# FRDM-Shield-Rev1_1.net
KiCad netlist of a schematic drawn in EAGLE
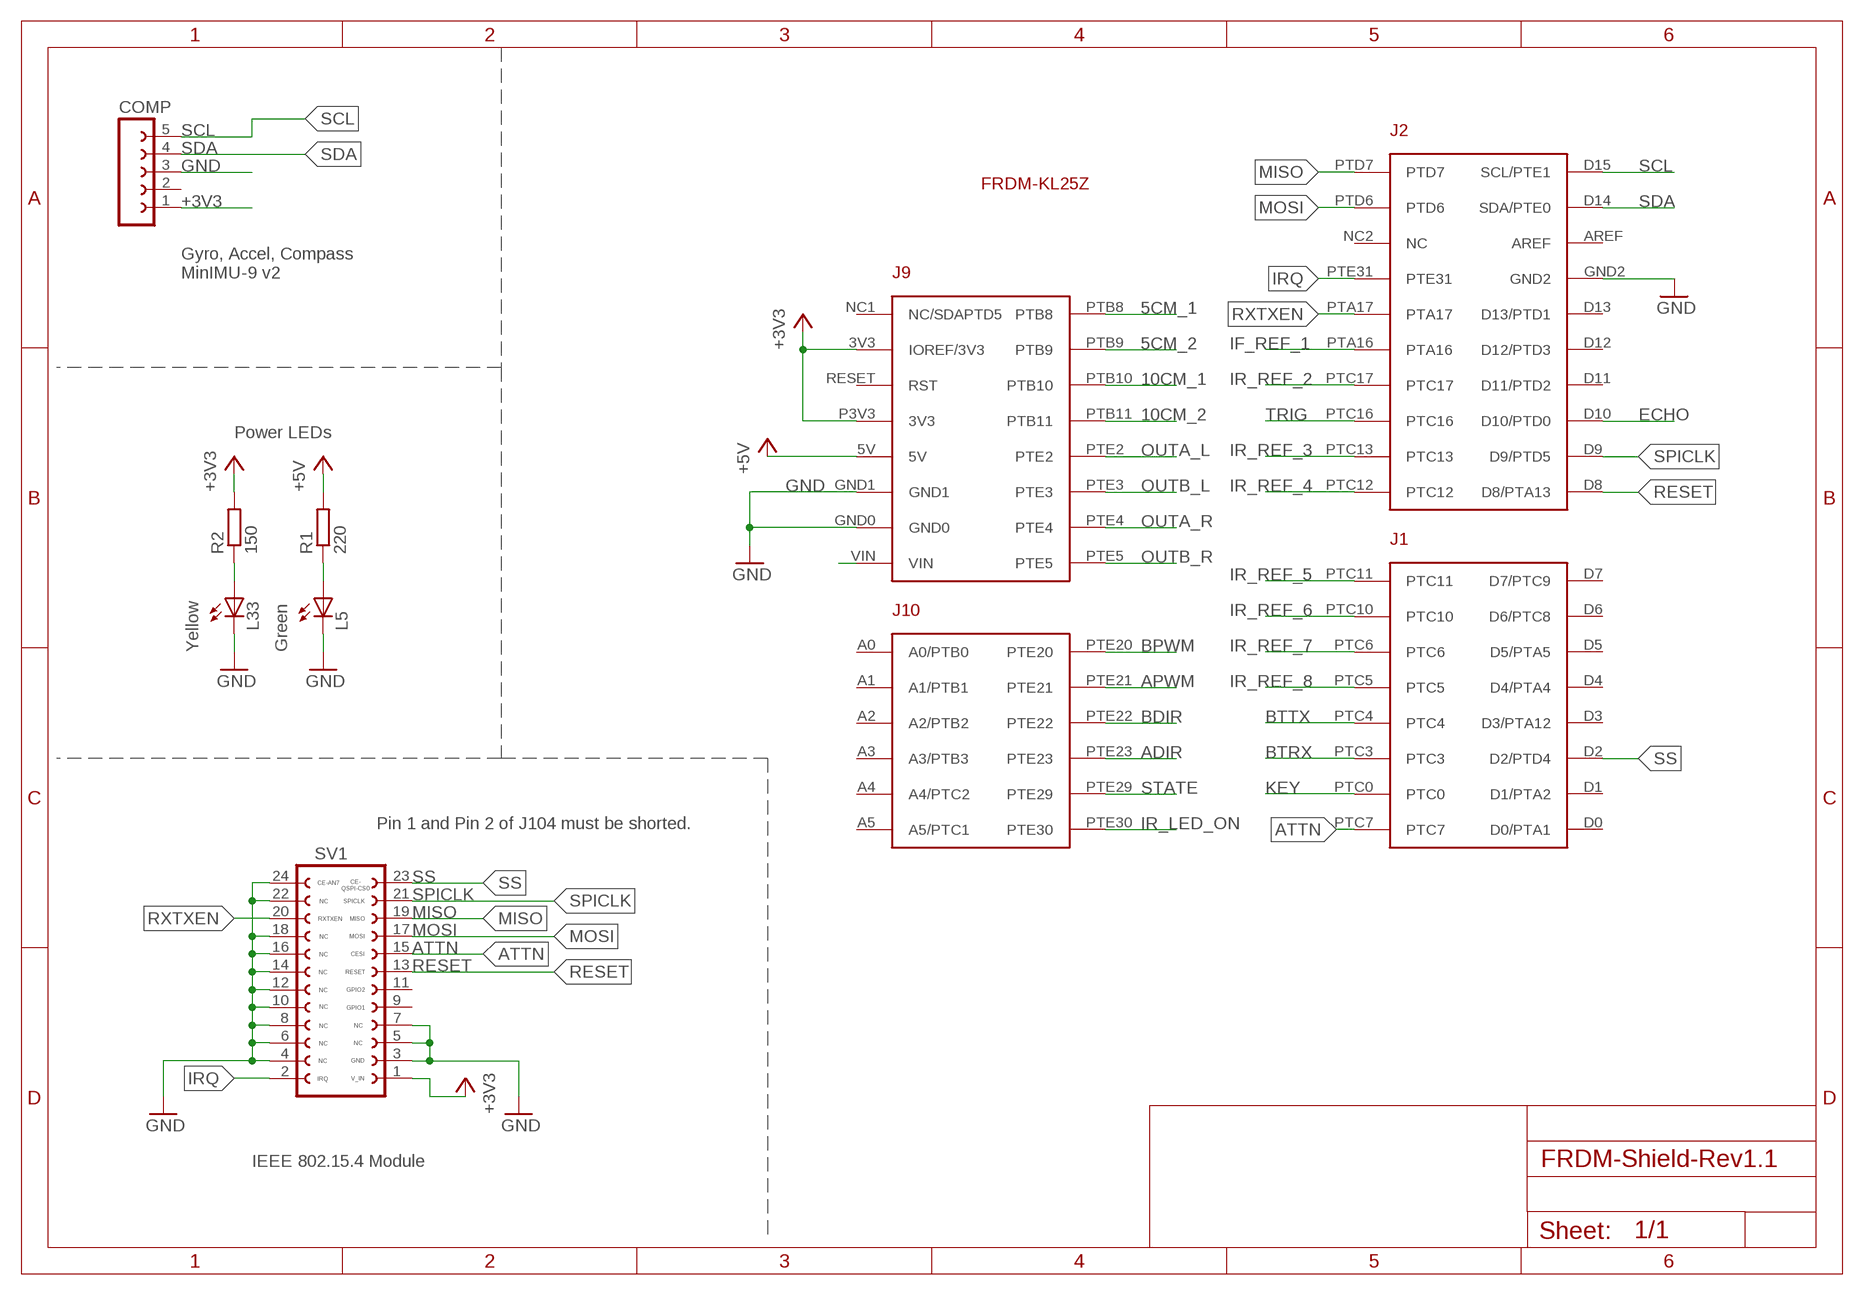
[diagram p0: schematic, sheet 1]

(export (version "E")
  (design (tool "Eeschema 10.0.6"))
  (components
    (comp (ref "COMP")
      (value "FE05-1")
      (footprint "eagle-import:FE05-1")
      (libsource (lib "eagle-import") (part "FE05-1"))
    )
    (comp (ref "FRDM1")
      (value "FRDM-KL25ZARDUINO")
      (footprint "eagle-import:FRDM-KL25Z")
      (libsource (lib "eagle-import") (part "FRDM-KL25ZARDUINO"))
    )
    (comp (ref "L5")
      (value "LEDCHIP-LED0603")
      (footprint "eagle-import:CHIP-LED0603")
      (libsource (lib "eagle-import") (part "LEDCHIP-LED0603"))
    )
    (comp (ref "L33")
      (value "LEDCHIP-LED0603")
      (footprint "eagle-import:CHIP-LED0603")
      (libsource (lib "eagle-import") (part "LEDCHIP-LED0603"))
    )
    (comp (ref "R1")
      (value "220")
      (footprint "eagle-import:M0805")
      (libsource (lib "eagle-import") (part "R-EU_M0805"))
    )
    (comp (ref "R2")
      (value "150")
      (footprint "eagle-import:M0805")
      (libsource (lib "eagle-import") (part "R-EU_M0805"))
    )
    (comp (ref "SV1")
      (value "MC1320X")
      (footprint "eagle-import:FE12-2")
      (libsource (lib "eagle-import") (part "MC1320X"))
    )
  )
  (nets
    (net (code "1") (name "+3V3") (class "Default")
      (node (ref "COMP") (pin "1") (pinfunction "1_1") (pintype "passive"))
      (node (ref "FRDM1") (pin "3V3") (pinfunction "IOREF/3V3_3V3") (pintype "bidirectional"))
      (node (ref "FRDM1") (pin "P3V3") (pinfunction "3V3_P3V3") (pintype "bidirectional"))
      (node (ref "R2") (pin "2") (pinfunction "2_2") (pintype "passive"))
      (node (ref "SV1") (pin "1") (pinfunction "1_1") (pintype "passive"))
    )
    (net (code "2") (name "+5V") (class "Default")
      (node (ref "FRDM1") (pin "5V") (pinfunction "5V_5V") (pintype "bidirectional"))
      (node (ref "R1") (pin "2") (pinfunction "2_2") (pintype "passive"))
    )
    (net (code "3") (name "/5CM_1") (class "Default")
      (node (ref "FRDM1") (pin "PTB8") (pinfunction "PTB8_PTB8") (pintype "bidirectional"))
    )
    (net (code "4") (name "/5CM_2") (class "Default")
      (node (ref "FRDM1") (pin "PTB9") (pinfunction "PTB9_PTB9") (pintype "bidirectional"))
    )
    (net (code "5") (name "/10CM_1") (class "Default")
      (node (ref "FRDM1") (pin "PTB10") (pinfunction "PTB10_PTB10") (pintype "bidirectional"))
    )
    (net (code "6") (name "/10CM_2") (class "Default")
      (node (ref "FRDM1") (pin "PTB11") (pinfunction "PTB11_PTB11") (pintype "bidirectional"))
    )
    (net (code "7") (name "/ADIR") (class "Default")
      (node (ref "FRDM1") (pin "PTE23") (pinfunction "PTE23_PTE23") (pintype "bidirectional"))
    )
    (net (code "8") (name "/APWM") (class "Default")
      (node (ref "FRDM1") (pin "PTE21") (pinfunction "PTE21_PTE21") (pintype "bidirectional"))
    )
    (net (code "9") (name "/BDIR") (class "Default")
      (node (ref "FRDM1") (pin "PTE22") (pinfunction "PTE22_PTE22") (pintype "bidirectional"))
    )
    (net (code "10") (name "/BPWM") (class "Default")
      (node (ref "FRDM1") (pin "PTE20") (pinfunction "PTE20_PTE20") (pintype "bidirectional"))
    )
    (net (code "11") (name "/BTRX") (class "Default")
      (node (ref "FRDM1") (pin "PTC3") (pinfunction "PTC3_PTC3") (pintype "bidirectional"))
    )
    (net (code "12") (name "/BTTX") (class "Default")
      (node (ref "FRDM1") (pin "PTC4") (pinfunction "PTC4_PTC4") (pintype "bidirectional"))
    )
    (net (code "13") (name "/ECHO") (class "Default")
      (node (ref "FRDM1") (pin "D10") (pinfunction "D10/PTD0_D10") (pintype "bidirectional"))
    )
    (net (code "14") (name "/IF_REF_1") (class "Default")
      (node (ref "FRDM1") (pin "PTA16") (pinfunction "PTA16_PTA16") (pintype "bidirectional"))
    )
    (net (code "15") (name "/IR_LED_ON") (class "Default")
      (node (ref "FRDM1") (pin "PTE30") (pinfunction "PTE30_PTE30") (pintype "bidirectional"))
    )
    (net (code "16") (name "/IR_REF_2") (class "Default")
      (node (ref "FRDM1") (pin "PTC17") (pinfunction "PTC17_PTC17") (pintype "bidirectional"))
    )
    (net (code "17") (name "/IR_REF_3") (class "Default")
      (node (ref "FRDM1") (pin "PTC13") (pinfunction "PTC13_PTC13") (pintype "bidirectional"))
    )
    (net (code "18") (name "/IR_REF_4") (class "Default")
      (node (ref "FRDM1") (pin "PTC12") (pinfunction "PTC12_PTC12") (pintype "bidirectional"))
    )
    (net (code "19") (name "/IR_REF_5") (class "Default")
      (node (ref "FRDM1") (pin "PTC11") (pinfunction "PTC11_PTC11") (pintype "bidirectional"))
    )
    (net (code "20") (name "/IR_REF_6") (class "Default")
      (node (ref "FRDM1") (pin "PTC10") (pinfunction "PTC10_PTC10") (pintype "bidirectional"))
    )
    (net (code "21") (name "/IR_REF_7") (class "Default")
      (node (ref "FRDM1") (pin "PTC6") (pinfunction "PTC6_PTC6") (pintype "bidirectional"))
    )
    (net (code "22") (name "/IR_REF_8") (class "Default")
      (node (ref "FRDM1") (pin "PTC5") (pinfunction "PTC5_PTC5") (pintype "bidirectional"))
    )
    (net (code "23") (name "/KEY") (class "Default")
      (node (ref "FRDM1") (pin "PTC0") (pinfunction "PTC0_PTC0") (pintype "bidirectional"))
    )
    (net (code "24") (name "/OUTA_L") (class "Default")
      (node (ref "FRDM1") (pin "PTE2") (pinfunction "PTE2_PTE2") (pintype "bidirectional"))
    )
    (net (code "25") (name "/OUTA_R") (class "Default")
      (node (ref "FRDM1") (pin "PTE4") (pinfunction "PTE4_PTE4") (pintype "bidirectional"))
    )
    (net (code "26") (name "/OUTB_L") (class "Default")
      (node (ref "FRDM1") (pin "PTE3") (pinfunction "PTE3_PTE3") (pintype "bidirectional"))
    )
    (net (code "27") (name "/OUTB_R") (class "Default")
      (node (ref "FRDM1") (pin "PTE5") (pinfunction "PTE5_PTE5") (pintype "bidirectional"))
    )
    (net (code "28") (name "/STATE") (class "Default")
      (node (ref "FRDM1") (pin "PTE29") (pinfunction "PTE29_PTE29") (pintype "bidirectional"))
    )
    (net (code "29") (name "/TRIG") (class "Default")
      (node (ref "FRDM1") (pin "PTC16") (pinfunction "PTC16_PTC16") (pintype "bidirectional"))
    )
    (net (code "30") (name "ATTN") (class "Default")
      (node (ref "FRDM1") (pin "PTC7") (pinfunction "PTC7_PTC7") (pintype "bidirectional"))
      (node (ref "SV1") (pin "15") (pinfunction "15_15") (pintype "passive"))
    )
    (net (code "31") (name "GND") (class "Default")
      (node (ref "COMP") (pin "3") (pinfunction "3_3") (pintype "passive"))
      (node (ref "FRDM1") (pin "GND0") (pinfunction "GND0_GND0") (pintype "bidirectional"))
      (node (ref "FRDM1") (pin "GND1") (pinfunction "GND1_GND1") (pintype "bidirectional"))
      (node (ref "FRDM1") (pin "GND2") (pinfunction "GND2_GND2") (pintype "bidirectional"))
      (node (ref "L33") (pin "C") (pinfunction "C_C") (pintype "passive"))
      (node (ref "L5") (pin "C") (pinfunction "C_C") (pintype "passive"))
      (node (ref "SV1") (pin "10") (pinfunction "10_10") (pintype "passive"))
      (node (ref "SV1") (pin "12") (pinfunction "12_12") (pintype "passive"))
      (node (ref "SV1") (pin "14") (pinfunction "14_14") (pintype "passive"))
      (node (ref "SV1") (pin "16") (pinfunction "16_16") (pintype "passive"))
      (node (ref "SV1") (pin "18") (pinfunction "18_18") (pintype "passive"))
      (node (ref "SV1") (pin "22") (pinfunction "22_22") (pintype "passive"))
      (node (ref "SV1") (pin "24") (pinfunction "24_24") (pintype "passive"))
      (node (ref "SV1") (pin "3") (pinfunction "3_3") (pintype "passive"))
      (node (ref "SV1") (pin "4") (pinfunction "4_4") (pintype "passive"))
      (node (ref "SV1") (pin "5") (pinfunction "5_5") (pintype "passive"))
      (node (ref "SV1") (pin "6") (pinfunction "6_6") (pintype "passive"))
      (node (ref "SV1") (pin "7") (pinfunction "7_7") (pintype "passive"))
      (node (ref "SV1") (pin "8") (pinfunction "8_8") (pintype "passive"))
    )
    (net (code "32") (name "IRQ") (class "Default")
      (node (ref "FRDM1") (pin "PTE31") (pinfunction "PTE31_PTE31") (pintype "bidirectional"))
      (node (ref "SV1") (pin "2") (pinfunction "2_2") (pintype "passive"))
    )
    (net (code "33") (name "MISO") (class "Default")
      (node (ref "FRDM1") (pin "PTD7") (pinfunction "PTD7_PTD7") (pintype "bidirectional"))
      (node (ref "SV1") (pin "19") (pinfunction "19_19") (pintype "passive"))
    )
    (net (code "34") (name "MOSI") (class "Default")
      (node (ref "FRDM1") (pin "PTD6") (pinfunction "PTD6_PTD6") (pintype "bidirectional"))
      (node (ref "SV1") (pin "17") (pinfunction "17_17") (pintype "passive"))
    )
    (net (code "35") (name "Net-(L5-PadA)") (class "Default")
      (node (ref "L5") (pin "A") (pinfunction "A_A") (pintype "passive"))
      (node (ref "R1") (pin "1") (pinfunction "1_1") (pintype "passive"))
    )
    (net (code "36") (name "Net-(L33-PadA)") (class "Default")
      (node (ref "L33") (pin "A") (pinfunction "A_A") (pintype "passive"))
      (node (ref "R2") (pin "1") (pinfunction "1_1") (pintype "passive"))
    )
    (net (code "37") (name "RESET") (class "Default")
      (node (ref "FRDM1") (pin "D8") (pinfunction "D8/PTA13_D8") (pintype "bidirectional"))
      (node (ref "SV1") (pin "13") (pinfunction "13_13") (pintype "passive"))
    )
    (net (code "38") (name "RXTXEN") (class "Default")
      (node (ref "FRDM1") (pin "PTA17") (pinfunction "PTA17_PTA17") (pintype "bidirectional"))
      (node (ref "SV1") (pin "20") (pinfunction "20_20") (pintype "passive"))
    )
    (net (code "39") (name "SCL") (class "Default")
      (node (ref "COMP") (pin "5") (pinfunction "5_5") (pintype "passive"))
      (node (ref "FRDM1") (pin "D15") (pinfunction "SCL/PTE1_D15") (pintype "bidirectional"))
    )
    (net (code "40") (name "SDA") (class "Default")
      (node (ref "COMP") (pin "4") (pinfunction "4_4") (pintype "passive"))
      (node (ref "FRDM1") (pin "D14") (pinfunction "SDA/PTE0_D14") (pintype "bidirectional"))
    )
    (net (code "41") (name "SPICLK") (class "Default")
      (node (ref "FRDM1") (pin "D9") (pinfunction "D9/PTD5_D9") (pintype "bidirectional"))
      (node (ref "SV1") (pin "21") (pinfunction "21_21") (pintype "passive"))
    )
    (net (code "42") (name "SS") (class "Default")
      (node (ref "FRDM1") (pin "D2") (pinfunction "D2/PTD4_D2") (pintype "bidirectional"))
      (node (ref "SV1") (pin "23") (pinfunction "23_23") (pintype "passive"))
    )
    (net (code "43") (name "unconnected-(COMP-Pad2)") (class "Default")
      (node (ref "COMP") (pin "2") (pinfunction "2_2") (pintype "passive"))
    )
    (net (code "44") (name "unconnected-(FRDM1-A0{slash}PTB0-PadA0)") (class "Default")
      (node (ref "FRDM1") (pin "A0") (pinfunction "A0/PTB0_A0") (pintype "bidirectional"))
    )
    (net (code "45") (name "unconnected-(FRDM1-A1{slash}PTB1-PadA1)") (class "Default")
      (node (ref "FRDM1") (pin "A1") (pinfunction "A1/PTB1_A1") (pintype "bidirectional"))
    )
    (net (code "46") (name "unconnected-(FRDM1-A2{slash}PTB2-PadA2)") (class "Default")
      (node (ref "FRDM1") (pin "A2") (pinfunction "A2/PTB2_A2") (pintype "bidirectional"))
    )
    (net (code "47") (name "unconnected-(FRDM1-A3{slash}PTB3-PadA3)") (class "Default")
      (node (ref "FRDM1") (pin "A3") (pinfunction "A3/PTB3_A3") (pintype "bidirectional"))
    )
    (net (code "48") (name "unconnected-(FRDM1-A4{slash}PTC2-PadA4)") (class "Default")
      (node (ref "FRDM1") (pin "A4") (pinfunction "A4/PTC2_A4") (pintype "bidirectional"))
    )
    (net (code "49") (name "unconnected-(FRDM1-A5{slash}PTC1-PadA5)") (class "Default")
      (node (ref "FRDM1") (pin "A5") (pinfunction "A5/PTC1_A5") (pintype "bidirectional"))
    )
    (net (code "50") (name "unconnected-(FRDM1-D0{slash}PTA1-PadD0)") (class "Default")
      (node (ref "FRDM1") (pin "D0") (pinfunction "D0/PTA1_D0") (pintype "bidirectional"))
    )
    (net (code "51") (name "unconnected-(FRDM1-D1{slash}PTA2-PadD1)") (class "Default")
      (node (ref "FRDM1") (pin "D1") (pinfunction "D1/PTA2_D1") (pintype "bidirectional"))
    )
    (net (code "52") (name "unconnected-(FRDM1-D3{slash}PTA12-PadD3)") (class "Default")
      (node (ref "FRDM1") (pin "D3") (pinfunction "D3/PTA12_D3") (pintype "bidirectional"))
    )
    (net (code "53") (name "unconnected-(FRDM1-D4{slash}PTA4-PadD4)") (class "Default")
      (node (ref "FRDM1") (pin "D4") (pinfunction "D4/PTA4_D4") (pintype "bidirectional"))
    )
    (net (code "54") (name "unconnected-(FRDM1-D5{slash}PTA5-PadD5)") (class "Default")
      (node (ref "FRDM1") (pin "D5") (pinfunction "D5/PTA5_D5") (pintype "bidirectional"))
    )
    (net (code "55") (name "unconnected-(FRDM1-D6{slash}PTC8-PadD6)") (class "Default")
      (node (ref "FRDM1") (pin "D6") (pinfunction "D6/PTC8_D6") (pintype "bidirectional"))
    )
    (net (code "56") (name "unconnected-(FRDM1-D7{slash}PTC9-PadD7)") (class "Default")
      (node (ref "FRDM1") (pin "D7") (pinfunction "D7/PTC9_D7") (pintype "bidirectional"))
    )
    (net (code "57") (name "unconnected-(FRDM1-D11{slash}PTD2-PadD11)") (class "Default")
      (node (ref "FRDM1") (pin "D11") (pinfunction "D11/PTD2_D11") (pintype "bidirectional"))
    )
    (net (code "58") (name "unconnected-(FRDM1-D12{slash}PTD3-PadD12)") (class "Default")
      (node (ref "FRDM1") (pin "D12") (pinfunction "D12/PTD3_D12") (pintype "bidirectional"))
    )
    (net (code "59") (name "unconnected-(FRDM1-D13{slash}PTD1-PadD13)") (class "Default")
      (node (ref "FRDM1") (pin "D13") (pinfunction "D13/PTD1_D13") (pintype "bidirectional"))
    )
    (net (code "60") (name "unconnected-(FRDM1-NC-PadNC2)") (class "Default")
      (node (ref "FRDM1") (pin "NC2") (pinfunction "NC_NC2") (pintype "bidirectional"))
    )
    (net (code "61") (name "unconnected-(FRDM1-NC{slash}SDAPTD5-PadNC1)") (class "Default")
      (node (ref "FRDM1") (pin "NC1") (pinfunction "NC/SDAPTD5_NC1") (pintype "bidirectional"))
    )
    (net (code "62") (name "unconnected-(FRDM1-PadAREF)") (class "Default")
      (node (ref "FRDM1") (pin "AREF") (pinfunction "AREF_AREF") (pintype "bidirectional"))
    )
    (net (code "63") (name "unconnected-(FRDM1-PadVIN)") (class "Default")
      (node (ref "FRDM1") (pin "VIN") (pinfunction "VIN_VIN") (pintype "bidirectional"))
    )
    (net (code "64") (name "unconnected-(FRDM1-RST-PadRESET)") (class "Default")
      (node (ref "FRDM1") (pin "RESET") (pinfunction "RST_RESET") (pintype "bidirectional"))
    )
    (net (code "65") (name "unconnected-(SV1-Pad9)") (class "Default")
      (node (ref "SV1") (pin "9") (pinfunction "9_9") (pintype "passive"))
    )
    (net (code "66") (name "unconnected-(SV1-Pad11)") (class "Default")
      (node (ref "SV1") (pin "11") (pinfunction "11_11") (pintype "passive"))
    )
  )
)
